# drive_subsystem.net
KiCad netlist of a schematic drawn in EAGLE
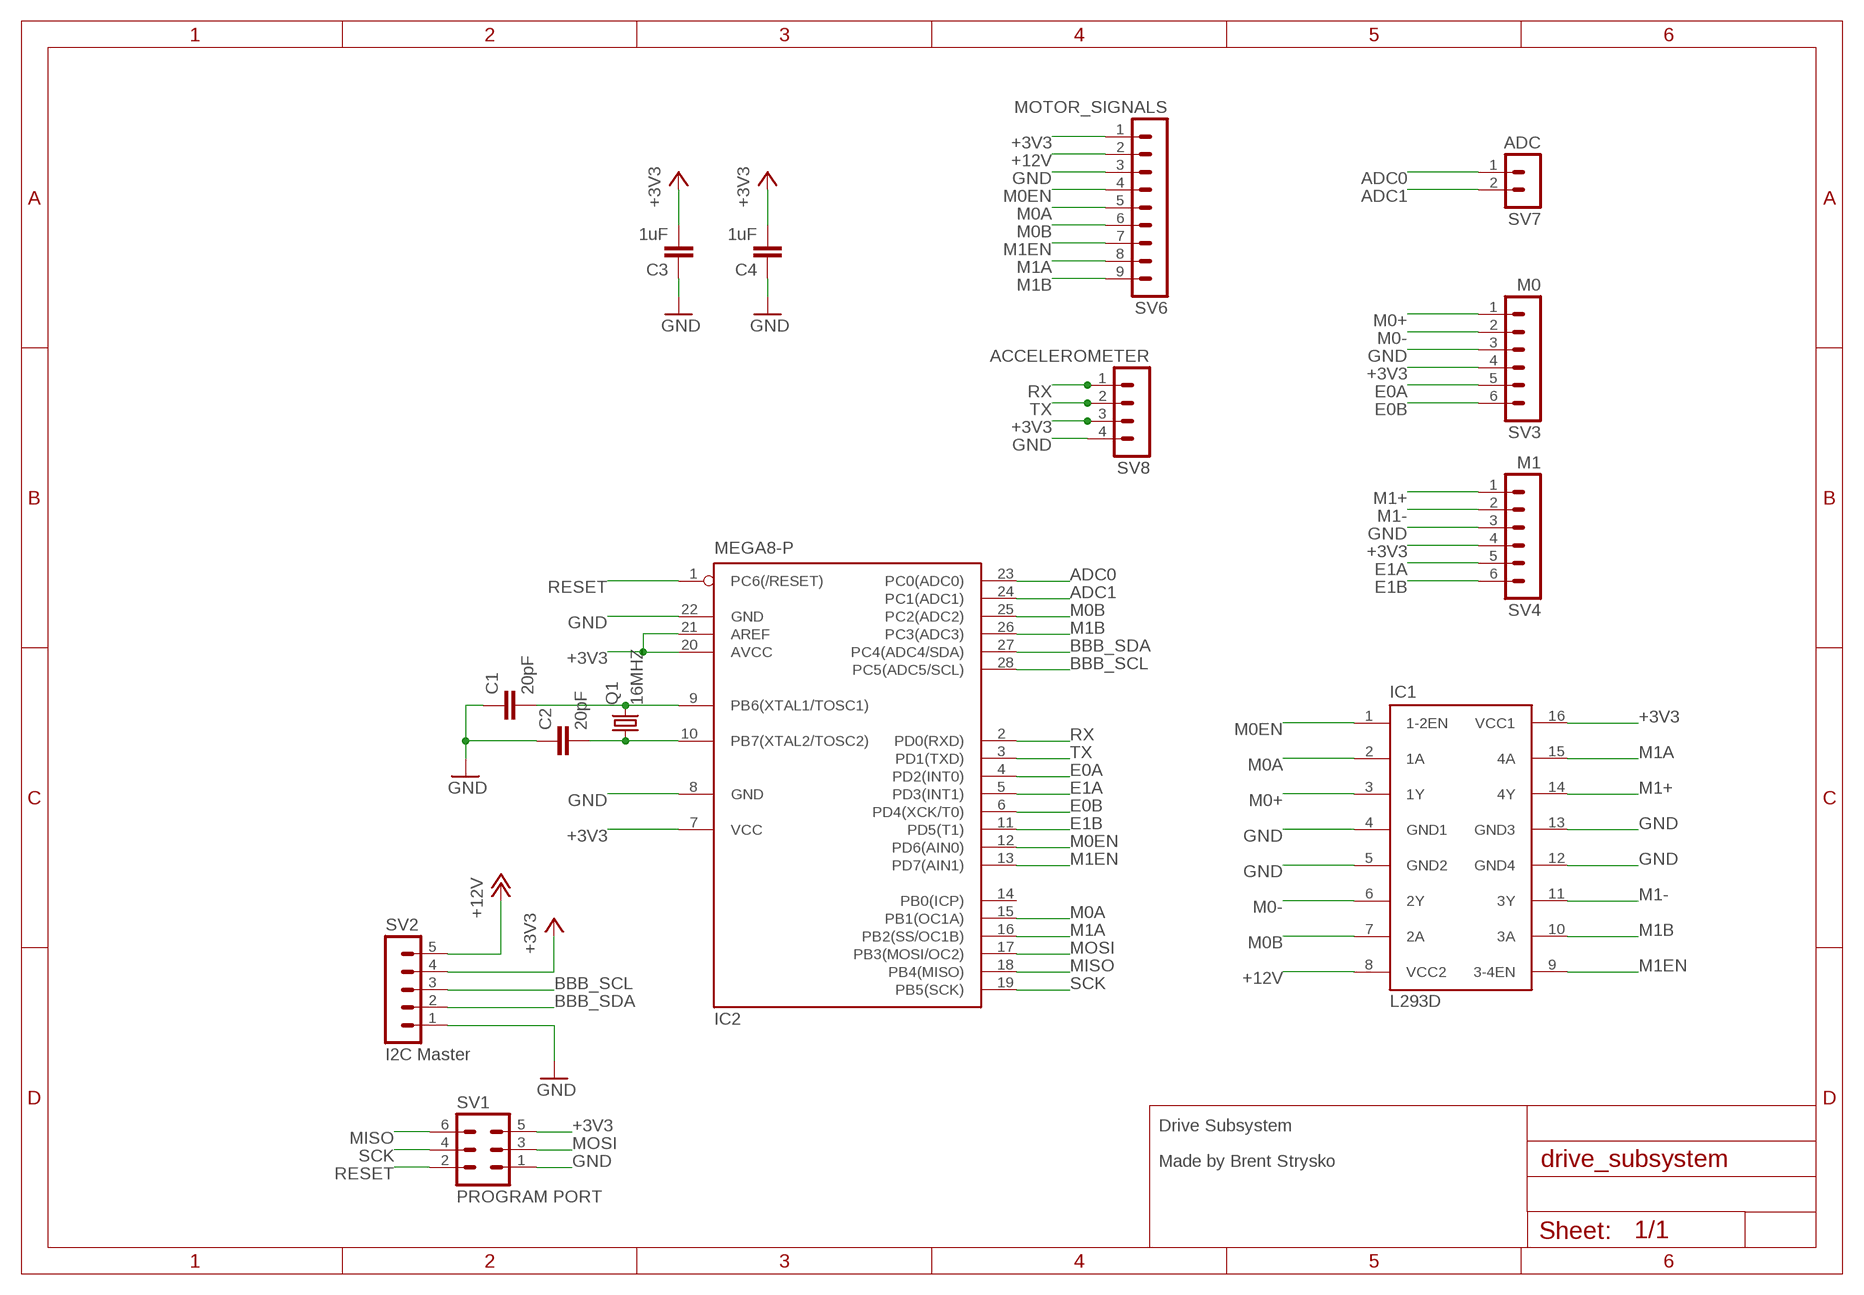
[diagram p0: schematic, sheet 1]

(export (version "E")
  (design (tool "Eeschema 10.0.6"))
  (components
    (comp (ref "C1")
      (value "20pF")
      (footprint "eagle-import:CAP-PTH-SMALL-KIT")
      (libsource (lib "eagle-import") (part "CAPKIT"))
    )
    (comp (ref "C2")
      (value "20pF")
      (footprint "eagle-import:CAP-PTH-SMALL-KIT")
      (libsource (lib "eagle-import") (part "CAPKIT"))
    )
    (comp (ref "C3")
      (value "1uF")
      (footprint "eagle-import:CAP-PTH-SMALL-KIT")
      (libsource (lib "eagle-import") (part "CAPKIT"))
    )
    (comp (ref "C4")
      (value "1uF")
      (footprint "eagle-import:CAP-PTH-SMALL-KIT")
      (libsource (lib "eagle-import") (part "CAPKIT"))
    )
    (comp (ref "IC1")
      (value "L293D")
      (footprint "eagle-import:DIL16")
      (libsource (lib "eagle-import") (part "L293D"))
    )
    (comp (ref "IC2")
      (value "MEGA8-P")
      (footprint "eagle-import:DIL28-3")
      (libsource (lib "eagle-import") (part "MEGA8-P"))
    )
    (comp (ref "Q1")
      (value "16MHZ")
      (footprint "eagle-import:HC49U-V")
      (libsource (lib "eagle-import") (part "CRYSTALHC49U-V"))
    )
    (comp (ref "SV1")
      (value "PROGRAM PORT")
      (footprint "eagle-import:MA03-2")
      (libsource (lib "eagle-import") (part "MA03-2"))
    )
    (comp (ref "SV2")
      (value "I2C Master")
      (footprint "eagle-import:MA05-1")
      (libsource (lib "eagle-import") (part "MA05-1"))
    )
    (comp (ref "SV3")
      (value "M0")
      (footprint "eagle-import:MA06-1")
      (libsource (lib "eagle-import") (part "MA06-1"))
    )
    (comp (ref "SV4")
      (value "M1")
      (footprint "eagle-import:MA06-1")
      (libsource (lib "eagle-import") (part "MA06-1"))
    )
    (comp (ref "SV6")
      (value "MOTOR_SIGNALS")
      (footprint "eagle-import:MA09-1")
      (libsource (lib "eagle-import") (part "MA09-1"))
    )
    (comp (ref "SV7")
      (value "ADC")
      (footprint "eagle-import:MA02-1")
      (libsource (lib "eagle-import") (part "MA02-1"))
    )
    (comp (ref "SV8")
      (value "ACCELEROMETER")
      (footprint "eagle-import:MA04-1")
      (libsource (lib "eagle-import") (part "MA04-1"))
    )
  )
  (nets
    (net (code "1") (name "+3V3") (class "Default")
      (node (ref "C3") (pin "2") (pinfunction "2_2") (pintype "passive"))
      (node (ref "C4") (pin "2") (pinfunction "2_2") (pintype "passive"))
      (node (ref "IC1") (pin "16") (pinfunction "VCC1_16") (pintype "power_in"))
      (node (ref "IC2") (pin "20") (pinfunction "AVCC_20") (pintype "power_in"))
      (node (ref "IC2") (pin "21") (pinfunction "AREF_21") (pintype "passive"))
      (node (ref "IC2") (pin "7") (pinfunction "VCC_7") (pintype "power_in"))
      (node (ref "SV1") (pin "5") (pinfunction "5_5") (pintype "passive"))
      (node (ref "SV2") (pin "4") (pinfunction "4_4") (pintype "passive"))
      (node (ref "SV3") (pin "4") (pinfunction "4_4") (pintype "passive"))
      (node (ref "SV4") (pin "4") (pinfunction "4_4") (pintype "passive"))
      (node (ref "SV6") (pin "1") (pinfunction "1_1") (pintype "passive"))
      (node (ref "SV8") (pin "3") (pinfunction "3_3") (pintype "passive"))
    )
    (net (code "2") (name "+12V") (class "Default")
      (node (ref "IC1") (pin "8") (pinfunction "VCC2_8") (pintype "power_in"))
      (node (ref "SV2") (pin "5") (pinfunction "5_5") (pintype "passive"))
      (node (ref "SV6") (pin "2") (pinfunction "2_2") (pintype "passive"))
    )
    (net (code "3") (name "/ADC0") (class "Default")
      (node (ref "IC2") (pin "23") (pinfunction "PC0(ADC0)_23") (pintype "bidirectional"))
      (node (ref "SV7") (pin "1") (pinfunction "1_1") (pintype "passive"))
    )
    (net (code "4") (name "/ADC1") (class "Default")
      (node (ref "IC2") (pin "24") (pinfunction "PC1(ADC1)_24") (pintype "bidirectional"))
      (node (ref "SV7") (pin "2") (pinfunction "2_2") (pintype "passive"))
    )
    (net (code "5") (name "/BBB_SCL") (class "Default")
      (node (ref "IC2") (pin "28") (pinfunction "PC5(ADC5/SCL)_28") (pintype "bidirectional"))
      (node (ref "SV2") (pin "3") (pinfunction "3_3") (pintype "passive"))
    )
    (net (code "6") (name "/BBB_SDA") (class "Default")
      (node (ref "IC2") (pin "27") (pinfunction "PC4(ADC4/SDA)_27") (pintype "bidirectional"))
      (node (ref "SV2") (pin "2") (pinfunction "2_2") (pintype "passive"))
    )
    (net (code "7") (name "/E0A") (class "Default")
      (node (ref "IC2") (pin "4") (pinfunction "PD2(INT0)_4") (pintype "bidirectional"))
      (node (ref "SV3") (pin "5") (pinfunction "5_5") (pintype "passive"))
    )
    (net (code "8") (name "/E0B") (class "Default")
      (node (ref "IC2") (pin "6") (pinfunction "PD4(XCK/T0)_6") (pintype "bidirectional"))
      (node (ref "SV3") (pin "6") (pinfunction "6_6") (pintype "passive"))
    )
    (net (code "9") (name "/E1A") (class "Default")
      (node (ref "IC2") (pin "5") (pinfunction "PD3(INT1)_5") (pintype "bidirectional"))
      (node (ref "SV4") (pin "5") (pinfunction "5_5") (pintype "passive"))
    )
    (net (code "10") (name "/E1B") (class "Default")
      (node (ref "IC2") (pin "11") (pinfunction "PD5(T1)_11") (pintype "bidirectional"))
      (node (ref "SV4") (pin "6") (pinfunction "6_6") (pintype "passive"))
    )
    (net (code "11") (name "/M0+") (class "Default")
      (node (ref "IC1") (pin "3") (pinfunction "1Y_3") (pintype "output"))
      (node (ref "SV3") (pin "1") (pinfunction "1_1") (pintype "passive"))
    )
    (net (code "12") (name "/M0-") (class "Default")
      (node (ref "IC1") (pin "6") (pinfunction "2Y_6") (pintype "output"))
      (node (ref "SV3") (pin "2") (pinfunction "2_2") (pintype "passive"))
    )
    (net (code "13") (name "/M0A") (class "Default")
      (node (ref "IC1") (pin "2") (pinfunction "1A_2") (pintype "input"))
      (node (ref "IC2") (pin "15") (pinfunction "PB1(OC1A)_15") (pintype "bidirectional"))
      (node (ref "SV6") (pin "5") (pinfunction "5_5") (pintype "passive"))
    )
    (net (code "14") (name "/M0B") (class "Default")
      (node (ref "IC1") (pin "7") (pinfunction "2A_7") (pintype "input"))
      (node (ref "IC2") (pin "25") (pinfunction "PC2(ADC2)_25") (pintype "bidirectional"))
      (node (ref "SV6") (pin "6") (pinfunction "6_6") (pintype "passive"))
    )
    (net (code "15") (name "/M0EN") (class "Default")
      (node (ref "IC1") (pin "1") (pinfunction "1-2EN_1") (pintype "input"))
      (node (ref "IC2") (pin "12") (pinfunction "PD6(AIN0)_12") (pintype "bidirectional"))
      (node (ref "SV6") (pin "4") (pinfunction "4_4") (pintype "passive"))
    )
    (net (code "16") (name "/M1+") (class "Default")
      (node (ref "IC1") (pin "14") (pinfunction "4Y_14") (pintype "output"))
      (node (ref "SV4") (pin "1") (pinfunction "1_1") (pintype "passive"))
    )
    (net (code "17") (name "/M1-") (class "Default")
      (node (ref "IC1") (pin "11") (pinfunction "3Y_11") (pintype "output"))
      (node (ref "SV4") (pin "2") (pinfunction "2_2") (pintype "passive"))
    )
    (net (code "18") (name "/M1A") (class "Default")
      (node (ref "IC1") (pin "15") (pinfunction "4A_15") (pintype "input"))
      (node (ref "IC2") (pin "16") (pinfunction "PB2(SS/OC1B)_16") (pintype "bidirectional"))
      (node (ref "SV6") (pin "8") (pinfunction "8_8") (pintype "passive"))
    )
    (net (code "19") (name "/M1B") (class "Default")
      (node (ref "IC1") (pin "10") (pinfunction "3A_10") (pintype "input"))
      (node (ref "IC2") (pin "26") (pinfunction "PC3(ADC3)_26") (pintype "bidirectional"))
      (node (ref "SV6") (pin "9") (pinfunction "9_9") (pintype "passive"))
    )
    (net (code "20") (name "/M1EN") (class "Default")
      (node (ref "IC1") (pin "9") (pinfunction "3-4EN_9") (pintype "input"))
      (node (ref "IC2") (pin "13") (pinfunction "PD7(AIN1)_13") (pintype "bidirectional"))
      (node (ref "SV6") (pin "7") (pinfunction "7_7") (pintype "passive"))
    )
    (net (code "21") (name "/MISO") (class "Default")
      (node (ref "IC2") (pin "18") (pinfunction "PB4(MISO)_18") (pintype "bidirectional"))
      (node (ref "SV1") (pin "6") (pinfunction "6_6") (pintype "passive"))
    )
    (net (code "22") (name "/MOSI") (class "Default")
      (node (ref "IC2") (pin "17") (pinfunction "PB3(MOSI/OC2)_17") (pintype "bidirectional"))
      (node (ref "SV1") (pin "3") (pinfunction "3_3") (pintype "passive"))
    )
    (net (code "23") (name "/RESET") (class "Default")
      (node (ref "IC2") (pin "1") (pinfunction "PC6(/RESET)_1") (pintype "bidirectional"))
      (node (ref "SV1") (pin "2") (pinfunction "2_2") (pintype "passive"))
    )
    (net (code "24") (name "/RX") (class "Default")
      (node (ref "IC2") (pin "2") (pinfunction "PD0(RXD)_2") (pintype "bidirectional"))
      (node (ref "SV8") (pin "1") (pinfunction "1_1") (pintype "passive"))
    )
    (net (code "25") (name "/SCK") (class "Default")
      (node (ref "IC2") (pin "19") (pinfunction "PB5(SCK)_19") (pintype "bidirectional"))
      (node (ref "SV1") (pin "4") (pinfunction "4_4") (pintype "passive"))
    )
    (net (code "26") (name "/TX") (class "Default")
      (node (ref "IC2") (pin "3") (pinfunction "PD1(TXD)_3") (pintype "bidirectional"))
      (node (ref "SV8") (pin "2") (pinfunction "2_2") (pintype "passive"))
    )
    (net (code "27") (name "GND") (class "Default")
      (node (ref "C1") (pin "1") (pinfunction "1_1") (pintype "passive"))
      (node (ref "C2") (pin "1") (pinfunction "1_1") (pintype "passive"))
      (node (ref "C3") (pin "1") (pinfunction "1_1") (pintype "passive"))
      (node (ref "C4") (pin "1") (pinfunction "1_1") (pintype "passive"))
      (node (ref "IC1") (pin "12") (pinfunction "GND4_12") (pintype "power_in"))
      (node (ref "IC1") (pin "13") (pinfunction "GND3_13") (pintype "power_in"))
      (node (ref "IC1") (pin "4") (pinfunction "GND1_4") (pintype "power_in"))
      (node (ref "IC1") (pin "5") (pinfunction "GND2_5") (pintype "power_in"))
      (node (ref "IC2") (pin "22") (pinfunction "GND_22") (pintype "power_in"))
      (node (ref "IC2") (pin "8") (pinfunction "GND_8") (pintype "power_in"))
      (node (ref "SV1") (pin "1") (pinfunction "1_1") (pintype "passive"))
      (node (ref "SV2") (pin "1") (pinfunction "1_1") (pintype "passive"))
      (node (ref "SV3") (pin "3") (pinfunction "3_3") (pintype "passive"))
      (node (ref "SV4") (pin "3") (pinfunction "3_3") (pintype "passive"))
      (node (ref "SV6") (pin "3") (pinfunction "3_3") (pintype "passive"))
      (node (ref "SV8") (pin "4") (pinfunction "4_4") (pintype "passive"))
    )
    (net (code "28") (name "Net-(IC2-PB6(XTAL1{slash}TOSC1))") (class "Default")
      (node (ref "C1") (pin "2") (pinfunction "2_2") (pintype "passive"))
      (node (ref "IC2") (pin "9") (pinfunction "PB6(XTAL1/TOSC1)_9") (pintype "bidirectional"))
      (node (ref "Q1") (pin "2") (pinfunction "2_2") (pintype "passive"))
    )
    (net (code "29") (name "Net-(IC2-PB7(XTAL2{slash}TOSC2))") (class "Default")
      (node (ref "C2") (pin "2") (pinfunction "2_2") (pintype "passive"))
      (node (ref "IC2") (pin "10") (pinfunction "PB7(XTAL2/TOSC2)_10") (pintype "bidirectional"))
      (node (ref "Q1") (pin "1") (pinfunction "1_1") (pintype "passive"))
    )
    (net (code "30") (name "unconnected-(IC2-PB0(ICP)-Pad14)") (class "Default")
      (node (ref "IC2") (pin "14") (pinfunction "PB0(ICP)_14") (pintype "bidirectional"))
    )
  )
)
